# Input_channel.net
KiCad netlist of a schematic drawn in Altium Designer
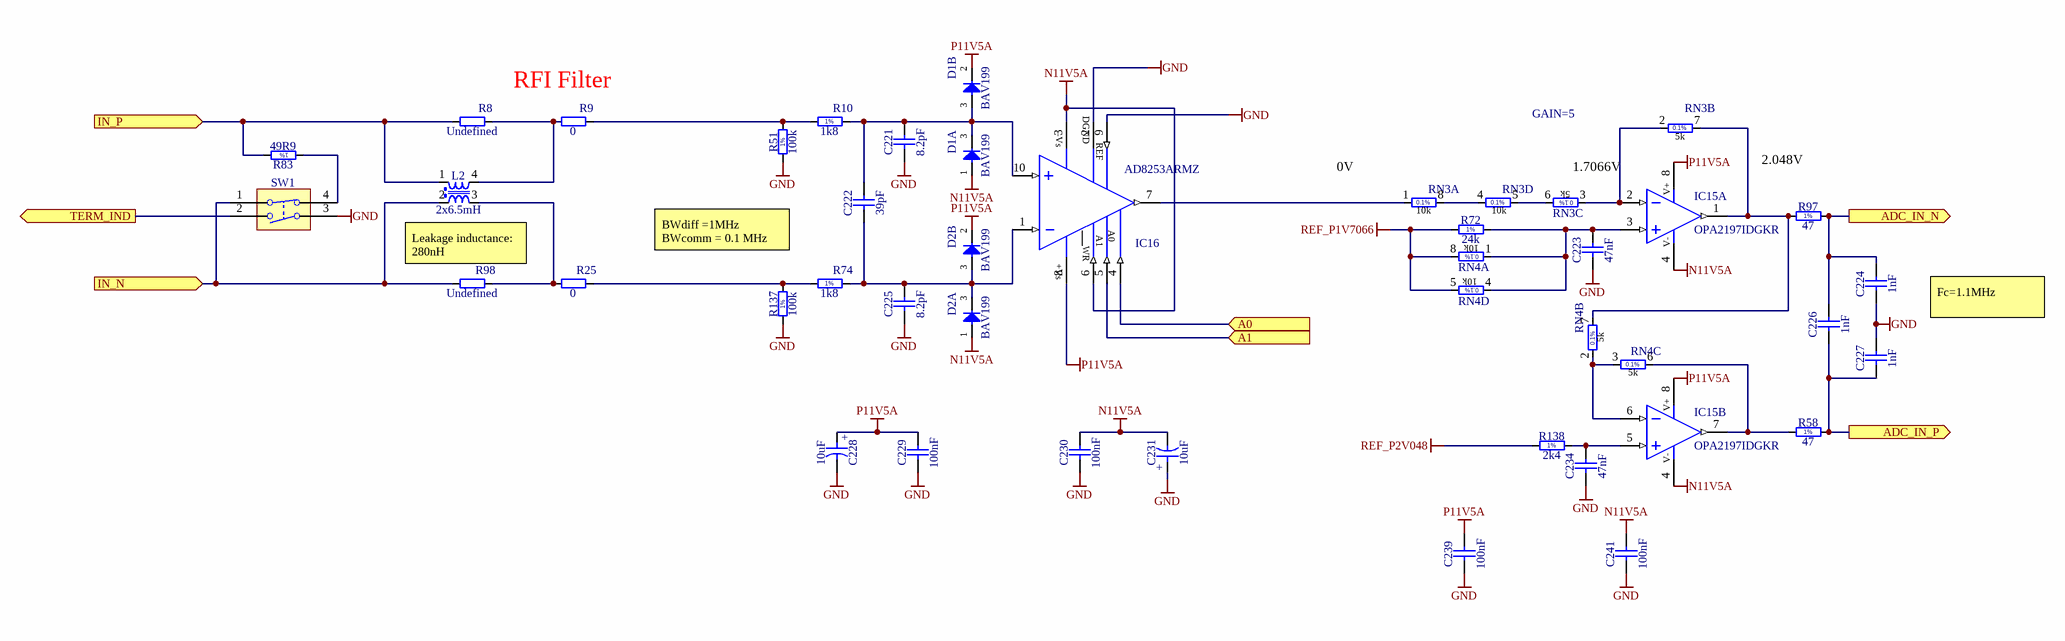
[diagram p0: Input_channel.SchDoc]

(export (version "E")
  (design (tool "Eeschema 10.0.6"))
  (components
    (comp (ref "C221")
      (value "8.2pF")
      (footprint "CAPC1608X87N")
      (description "Non-polarised capacitor")
      (fields
        (field (name "PART NUMBER") "CC0603_8.2PF_50V_0.5PF_NP0")
        (field (name "VOLTAGE") "50V")
        (field (name "AUTHOR") "CERN DEM JLC")
      )
      (libsource (lib "Capacitors") (part "Capacitor - non polarized"))
    )
    (comp (ref "C222")
      (value "39pF")
      (footprint "CAPC1608X87N")
      (description "Non-polarised capacitor")
      (fields
        (field (name "PART NUMBER") "CC0603_39PF_50V_5%_NP0")
        (field (name "VOLTAGE") "50V")
        (field (name "AUTHOR") "CERN DEM JLC")
      )
      (libsource (lib "Capacitors") (part "Capacitor - non polarized"))
    )
    (comp (ref "C223")
      (value "47nF")
      (footprint "CAPC2012X135N")
      (description "Non-polarised capacitor")
      (fields
        (field (name "PART NUMBER") "CC0805_47NF_25V_5%_C0G")
        (field (name "VOLTAGE") "25V")
        (field (name "AUTHOR") "CERN DEM JLC")
      )
      (libsource (lib "Capacitors") (part "Capacitor - non polarized"))
    )
    (comp (ref "C224")
      (value "1nF")
      (footprint "CAPC1608X90N")
      (description "Non-polarised capacitor")
      (fields
        (field (name "PART NUMBER") "CC0603_1NF_50V_1%_NP0")
        (field (name "VOLTAGE") "50V")
        (field (name "AUTHOR") "CERN DEM JLC")
      )
      (libsource (lib "Capacitors") (part "Capacitor - non polarized"))
    )
    (comp (ref "C225")
      (value "8.2pF")
      (footprint "CAPC1608X87N")
      (description "Non-polarised capacitor")
      (fields
        (field (name "PART NUMBER") "CC0603_8.2PF_50V_0.5PF_NP0")
        (field (name "VOLTAGE") "50V")
        (field (name "AUTHOR") "CERN DEM JLC")
      )
      (libsource (lib "Capacitors") (part "Capacitor - non polarized"))
    )
    (comp (ref "C226")
      (value "1nF")
      (footprint "CAPC1608X90N")
      (description "Non-polarised capacitor")
      (fields
        (field (name "PART NUMBER") "CC0603_1NF_50V_1%_NP0")
        (field (name "VOLTAGE") "50V")
        (field (name "AUTHOR") "CERN DEM JLC")
      )
      (libsource (lib "Capacitors") (part "Capacitor - non polarized"))
    )
    (comp (ref "C227")
      (value "1nF")
      (footprint "CAPC1608X90N")
      (description "Non-polarised capacitor")
      (fields
        (field (name "PART NUMBER") "CC0603_1NF_50V_1%_NP0")
        (field (name "VOLTAGE") "50V")
        (field (name "AUTHOR") "CERN DEM JLC")
      )
      (libsource (lib "Capacitors") (part "Capacitor - non polarized"))
    )
    (comp (ref "C228")
      (value "10uF")
      (footprint "CAPMP3216X180N")
      (description "Polarised capacitor")
      (fields
        (field (name "PART NUMBER") "CTE3216-18_10UF_16V_20%_AVX_TCJ")
        (field (name "VOLTAGE") "16V")
        (field (name "AUTHOR") "CERN DEM JLC")
      )
      (libsource (lib "Capacitors") (part "Capacitor - polarized"))
    )
    (comp (ref "C229")
      (value "100nF")
      (footprint "CAPC1005X55N")
      (description "Non-polarised capacitor")
      (fields
        (field (name "PART NUMBER") "CC0402_100NF_16V_10%_X7R")
        (field (name "VOLTAGE") "16V")
        (field (name "AUTHOR") "CERN DEM JLC")
      )
      (libsource (lib "Capacitors") (part "Capacitor - non polarized"))
    )
    (comp (ref "C230")
      (value "100nF")
      (footprint "CAPC1005X55N")
      (description "Non-polarised capacitor")
      (fields
        (field (name "PART NUMBER") "CC0402_100NF_16V_10%_X7R")
        (field (name "VOLTAGE") "16V")
        (field (name "AUTHOR") "CERN DEM JLC")
      )
      (libsource (lib "Capacitors") (part "Capacitor - non polarized"))
    )
    (comp (ref "C231")
      (value "10uF")
      (footprint "CAPMP3216X180N")
      (description "Polarised capacitor")
      (fields
        (field (name "PART NUMBER") "CTE3216-18_10UF_16V_20%_AVX_TCJ")
        (field (name "VOLTAGE") "16V")
        (field (name "AUTHOR") "CERN DEM JLC")
      )
      (libsource (lib "Capacitors") (part "Capacitor - polarized"))
    )
    (comp (ref "C234")
      (value "47nF")
      (footprint "CAPC2012X135N")
      (description "Non-polarised capacitor")
      (fields
        (field (name "PART NUMBER") "CC0805_47NF_25V_5%_C0G")
        (field (name "VOLTAGE") "25V")
        (field (name "AUTHOR") "CERN DEM JLC")
      )
      (libsource (lib "Capacitors") (part "Capacitor - non polarized"))
    )
    (comp (ref "C239")
      (value "100nF")
      (footprint "CAPC1005X55N")
      (description "Non-polarised capacitor")
      (fields
        (field (name "PART NUMBER") "CC0402_100NF_16V_10%_X7R")
        (field (name "VOLTAGE") "16V")
        (field (name "AUTHOR") "CERN DEM JLC")
      )
      (libsource (lib "Capacitors") (part "Capacitor - non polarized"))
    )
    (comp (ref "C241")
      (value "100nF")
      (footprint "CAPC1005X55N")
      (description "Non-polarised capacitor")
      (fields
        (field (name "PART NUMBER") "CC0402_100NF_16V_10%_X7R")
        (field (name "VOLTAGE") "16V")
        (field (name "AUTHOR") "CERN DEM JLC")
      )
      (libsource (lib "Capacitors") (part "Capacitor - non polarized"))
    )
    (comp (ref "D1")
      (value "BAV199")
      (footprint "SOT95P240X110-3N")
      (description "Serial Diode")
      (fields
        (field (name "VOLTAGE") "75V")
        (field (name "POWER") "250mW")
        (field (name "AUTHOR") "CERN DEM JMW")
      )
      (libsource (lib "ICs And Semiconductors") (part "Diode x2 A1C3_A3C2"))
    )
    (comp (ref "D2")
      (value "BAV199")
      (footprint "SOT95P240X110-3N")
      (description "Serial Diode")
      (fields
        (field (name "VOLTAGE") "75V")
        (field (name "POWER") "250mW")
        (field (name "AUTHOR") "CERN DEM JMW")
      )
      (libsource (lib "ICs And Semiconductors") (part "Diode x2 A1C3_A3C2"))
    )
    (comp (ref "IC15")
      (value "OPA2197IDGKR")
      (footprint "SOP65P490X110-8N")
      (description "36-V, Precision, Rail-to-Rail Input Output, Low Offset Voltage Op Amp 8-VSSOP")
      (fields (field (name "MANUFACTURER") "TEXAS INSTRUMENTS") (field (name "AUTHOR") "GK"))
      (libsource (lib "LIBRARY_SCH") (part "OA_OPA2197IDGKR"))
    )
    (comp (ref "IC16")
      (value "AD8253ARMZ")
      (footprint "SOP50P490X110-10N")
      (description "10MHz, 20V/us, G= 1, 10, 100, 1000 iCMOS Programmable Gain Instrumentation Amplifier")
      (fields (field (name "MANUFACTURER") "ANALOG DEVICES") (field (name "AUTHOR") "CERN DEM JLC"))
      (libsource (lib "ICs And Semiconductors") (part "AD8253"))
    )
    (comp (ref "L2")
      (value "2x6.5mH")
      (footprint "IND_WURTH_WE-SL2")
      (description "Inductor Common Mode")
      (fields
        (field (name "PART NUMBER") "IND_6.5MH_50%_WURTH_WE-SL2-744229")
        (field (name "POWER") "400mA")
        (field (name "AUTHOR") "CERN DEM JLC")
      )
      (libsource (lib "Inductors & Transformers") (part "Inductor Common Mode 1Dot-4 2Dot-3"))
    )
    (comp (ref "R8")
      (value "Undefined")
      (footprint "RESC1608X55N")
      (description "Resistor")
      (fields (field (name "PART NUMBER") "R0603_NO-VALUE") (field (name "AUTHOR") "CERN DEM JLC"))
      (libsource (lib "Resistors") (part "Resistor"))
    )
    (comp (ref "R9")
      (value "0")
      (footprint "RESC1608X55N")
      (description "Resistor")
      (fields
        (field (name "PART NUMBER") "R0603_0R_JUMPER")
        (field (name "MANUFACTURER") "GENERIC")
        (field (name "AUTHOR") "CERN DEM JLC")
      )
      (libsource (lib "Resistors") (part "Resistor"))
    )
    (comp (ref "R10")
      (value "1k8")
      (footprint "RESC1608X55N")
      (description "Resistor - 1%")
      (fields
        (field (name "PART NUMBER") "R0603_1K8_1%_0.1W_100PPM")
        (field (name "POWER") "0.1W")
        (field (name "AUTHOR") "CERN DEM JLC")
      )
      (libsource (lib "Resistors") (part "Resistor - 1%"))
    )
    (comp (ref "R25")
      (value "0")
      (footprint "RESC1608X55N")
      (description "Resistor")
      (fields
        (field (name "PART NUMBER") "R0603_0R_JUMPER")
        (field (name "MANUFACTURER") "GENERIC")
        (field (name "AUTHOR") "CERN DEM JLC")
      )
      (libsource (lib "Resistors") (part "Resistor"))
    )
    (comp (ref "R51")
      (value "100k")
      (footprint "RESC1608X55N")
      (description "Resistor - 1%")
      (fields
        (field (name "PART NUMBER") "R0603_100K_1%_0.1W_100PPM")
        (field (name "POWER") "0.1W")
        (field (name "AUTHOR") "CERN DEM JLC")
      )
      (libsource (lib "Resistors") (part "Resistor - 1%"))
    )
    (comp (ref "R58")
      (value "47")
      (footprint "RESC1005X40N")
      (description "Resistor - 1%")
      (fields
        (field (name "PART NUMBER") "R0402_47R_1%_0.0625W_100PPM")
        (field (name "POWER") "0.0625W")
        (field (name "AUTHOR") "CERN DEM JLC")
      )
      (libsource (lib "Resistors") (part "Resistor - 1%"))
    )
    (comp (ref "R72")
      (value "24k")
      (footprint "RESC1608X55N")
      (description "Resistor - 1%")
      (fields
        (field (name "PART NUMBER") "R0603_24K_1%_0.1W_100PPM")
        (field (name "POWER") "0.1W")
        (field (name "AUTHOR") "CERN DEM JLC")
      )
      (libsource (lib "Resistors") (part "Resistor - 1%"))
    )
    (comp (ref "R74")
      (value "1k8")
      (footprint "RESC1608X55N")
      (description "Resistor - 1%")
      (fields
        (field (name "PART NUMBER") "R0603_1K8_1%_0.1W_100PPM")
        (field (name "POWER") "0.1W")
        (field (name "AUTHOR") "CERN DEM JLC")
      )
      (libsource (lib "Resistors") (part "Resistor - 1%"))
    )
    (comp (ref "R83")
      (value "49R9")
      (footprint "RESC6331X70N")
      (description "Resistor - 1%")
      (fields
        (field (name "PART NUMBER") "R2512_49R9_1%_1W_100PPM_VISHAY_CRCW")
        (field (name "POWER") "1W")
        (field (name "AUTHOR") "CERN DEM JLC")
      )
      (libsource (lib "Resistors") (part "Resistor - 1%"))
    )
    (comp (ref "R97")
      (value "47")
      (footprint "RESC1005X40N")
      (description "Resistor - 1%")
      (fields
        (field (name "PART NUMBER") "R0402_47R_1%_0.0625W_100PPM")
        (field (name "POWER") "0.0625W")
        (field (name "AUTHOR") "CERN DEM JLC")
      )
      (libsource (lib "Resistors") (part "Resistor - 1%"))
    )
    (comp (ref "R98")
      (value "Undefined")
      (footprint "RESC1608X55N")
      (description "Resistor")
      (fields (field (name "PART NUMBER") "R0603_NO-VALUE") (field (name "AUTHOR") "CERN DEM JLC"))
      (libsource (lib "Resistors") (part "Resistor"))
    )
    (comp (ref "R137")
      (value "100k")
      (footprint "RESC1608X55N")
      (description "Resistor - 1%")
      (fields
        (field (name "PART NUMBER") "R0603_100K_1%_0.1W_100PPM")
        (field (name "POWER") "0.1W")
        (field (name "AUTHOR") "CERN DEM JLC")
      )
      (libsource (lib "Resistors") (part "Resistor - 1%"))
    )
    (comp (ref "R138")
      (value "2k4")
      (footprint "RESC1005X40N")
      (description "Resistor - 1%")
      (fields
        (field (name "PART NUMBER") "R0402_2K4_1%_0.0625W_100PPM")
        (field (name "POWER") "0.0625W")
        (field (name "AUTHOR") "CERN DEM JLC")
      )
      (libsource (lib "Resistors") (part "Resistor - 1%"))
    )
    (comp (ref "RN3")
      (value "10k 5K 5K 10K")
      (footprint "SOIC127P600X175-8N")
      (description "DIL8 Resistor Network 4 Resistors 10k-5k-5k-10k 0.1%")
      (fields
        (field (name "PART NUMBER") "RN_10K_5K_VISHAY_AORN2-1AT3")
        (field (name "POWER") "4x0.1W")
        (field (name "AUTHOR") "CERN DEM JLC")
      )
      (libsource (lib "Resistors") (part "RN DIL8_4xR_10k-5k-5k-10k_0.1%"))
    )
    (comp (ref "RN4")
      (value "10k 5K 5K 10K")
      (footprint "SOIC127P600X175-8N")
      (description "DIL8 Resistor Network 4 Resistors 10k-5k-5k-10k 0.1%")
      (fields
        (field (name "PART NUMBER") "RN_10K_5K_VISHAY_AORN2-1AT3")
        (field (name "POWER") "4x0.1W")
        (field (name "AUTHOR") "CERN DEM JLC")
      )
      (libsource (lib "Resistors") (part "RN DIL8_4xR_10k-5k-5k-10k_0.1%"))
    )
    (comp (ref "SW1")
      (value "Switch")
      (footprint "SW_CTS_204-121ST")
      (description "2x SPST DIP Switch 1NO + 1NF")
      (fields
        (field (name "PART NUMBER") "SW_CTS_204-121ST")
        (field (name "MANUFACTURER") "CTS")
        (field (name "AUTHOR") "CERN DEM JLC")
      )
      (libsource (lib "Eletro-mechanical") (part "SW_CTS_204-121ST"))
    )
  )
  (nets
    (net (code "1") (name "/A0") (class "Default")
      (node (ref "IC16") (pin "4") (pinfunction "A0_4") (pintype "input"))
    )
    (net (code "2") (name "/A1") (class "Default")
      (node (ref "IC16") (pin "5") (pinfunction "A1_5") (pintype "input"))
    )
    (net (code "3") (name "/ADC_IN_N") (class "Default")
      (node (ref "C224") (pin "2") (pinfunction "2_2") (pintype "passive"))
      (node (ref "C226") (pin "2") (pinfunction "2_2") (pintype "passive"))
      (node (ref "R97") (pin "2") (pinfunction "2_2") (pintype "passive"))
    )
    (net (code "4") (name "/ADC_IN_P") (class "Default")
      (node (ref "C226") (pin "1") (pinfunction "1_1") (pintype "passive"))
      (node (ref "C227") (pin "1") (pinfunction "1_1") (pintype "passive"))
      (node (ref "R58") (pin "2") (pinfunction "2_2") (pintype "passive"))
    )
    (net (code "5") (name "/IN_N") (class "Default")
      (node (ref "L2") (pin "2") (pinfunction "2_2") (pintype "passive"))
      (node (ref "R98") (pin "1") (pinfunction "1_1") (pintype "passive"))
      (node (ref "SW1") (pin "1") (pinfunction "1_1") (pintype "passive"))
    )
    (net (code "6") (name "/IN_P") (class "Default")
      (node (ref "L2") (pin "1") (pinfunction "1_1") (pintype "passive"))
      (node (ref "R8") (pin "1") (pinfunction "1_1") (pintype "passive"))
      (node (ref "R83") (pin "2") (pinfunction "2_2") (pintype "passive"))
    )
    (net (code "7") (name "/TERM_IND") (class "Default")
      (node (ref "SW1") (pin "2") (pinfunction "2_2") (pintype "passive"))
    )
    (net (code "8") (name "GND") (class "Default")
      (node (ref "C221") (pin "1") (pinfunction "1_1") (pintype "passive"))
      (node (ref "C223") (pin "1") (pinfunction "1_1") (pintype "passive"))
      (node (ref "C224") (pin "1") (pinfunction "1_1") (pintype "passive"))
      (node (ref "C225") (pin "1") (pinfunction "1_1") (pintype "passive"))
      (node (ref "C227") (pin "2") (pinfunction "2_2") (pintype "passive"))
      (node (ref "C228") (pin "2") (pinfunction "2_2") (pintype "passive"))
      (node (ref "C229") (pin "1") (pinfunction "1_1") (pintype "passive"))
      (node (ref "C230") (pin "1") (pinfunction "1_1") (pintype "passive"))
      (node (ref "C231") (pin "1") (pinfunction "1_1") (pintype "passive"))
      (node (ref "C234") (pin "1") (pinfunction "1_1") (pintype "passive"))
      (node (ref "C239") (pin "1") (pinfunction "1_1") (pintype "passive"))
      (node (ref "C241") (pin "1") (pinfunction "1_1") (pintype "passive"))
      (node (ref "IC16") (pin "2") (pinfunction "DGND_2") (pintype "power_in"))
      (node (ref "IC16") (pin "9") (pinfunction "REF_9") (pintype "input"))
      (node (ref "R137") (pin "1") (pinfunction "1_1") (pintype "passive"))
      (node (ref "R51") (pin "1") (pinfunction "1_1") (pintype "passive"))
      (node (ref "SW1") (pin "3") (pinfunction "3_3") (pintype "passive"))
    )
    (net (code "9") (name "N11V5A") (class "Default")
      (node (ref "C230") (pin "2") (pinfunction "2_2") (pintype "passive"))
      (node (ref "C231") (pin "2") (pinfunction "2_2") (pintype "passive"))
      (node (ref "C241") (pin "2") (pinfunction "2_2") (pintype "passive"))
      (node (ref "D1") (pin "1") (pinfunction "A_1") (pintype "passive"))
      (node (ref "D2") (pin "1") (pinfunction "A_1") (pintype "passive"))
      (node (ref "IC15") (pin "4") (pinfunction "V-_4") (pintype "power_in"))
      (node (ref "IC16") (pin "3") (pinfunction "-VS_3") (pintype "power_in"))
      (node (ref "IC16") (pin "6") (pinfunction "~{WR}_6") (pintype "input"))
    )
    (net (code "10") (name "Net-(D1A-COMAC)") (class "Default")
      (node (ref "C221") (pin "2") (pinfunction "2_2") (pintype "passive"))
      (node (ref "C222") (pin "2") (pinfunction "2_2") (pintype "passive"))
      (node (ref "D1") (pin "3") (pinfunction "COMAC_3") (pintype "passive"))
      (node (ref "IC16") (pin "10") (pinfunction "+IN_10") (pintype "input"))
      (node (ref "R10") (pin "2") (pinfunction "2_2") (pintype "passive"))
    )
    (net (code "11") (name "Net-(D2A-COMAC)") (class "Default")
      (node (ref "C222") (pin "1") (pinfunction "1_1") (pintype "passive"))
      (node (ref "C225") (pin "2") (pinfunction "2_2") (pintype "passive"))
      (node (ref "D2") (pin "3") (pinfunction "COMAC_3") (pintype "passive"))
      (node (ref "IC16") (pin "1") (pinfunction "-IN_1") (pintype "input"))
      (node (ref "R74") (pin "2") (pinfunction "2_2") (pintype "passive"))
    )
    (net (code "12") (name "Net-(IC15A-IN+)") (class "Default")
      (node (ref "C223") (pin "2") (pinfunction "2_2") (pintype "passive"))
      (node (ref "IC15") (pin "3") (pinfunction "IN+_3") (pintype "input"))
      (node (ref "R72") (pin "2") (pinfunction "2_2") (pintype "passive"))
      (node (ref "RN4") (pin "1") (pinfunction "1_1") (pintype "passive"))
      (node (ref "RN4") (pin "4") (pinfunction "4_4") (pintype "passive"))
    )
    (net (code "13") (name "Net-(IC15A-IN-)") (class "Default")
      (node (ref "IC15") (pin "2") (pinfunction "IN-_2") (pintype "input"))
      (node (ref "RN3") (pin "2") (pinfunction "2_2") (pintype "passive"))
      (node (ref "RN3") (pin "3") (pinfunction "3_3") (pintype "passive"))
    )
    (net (code "14") (name "Net-(IC15A-OUT)") (class "Default")
      (node (ref "IC15") (pin "1") (pinfunction "OUT_1") (pintype "output"))
      (node (ref "R97") (pin "1") (pinfunction "1_1") (pintype "passive"))
      (node (ref "RN3") (pin "7") (pinfunction "7_7") (pintype "passive"))
      (node (ref "RN4") (pin "7") (pinfunction "7_7") (pintype "passive"))
    )
    (net (code "15") (name "Net-(IC15B-IN+)") (class "Default")
      (node (ref "C234") (pin "2") (pinfunction "2_2") (pintype "passive"))
      (node (ref "IC15") (pin "5") (pinfunction "IN+_5") (pintype "input"))
      (node (ref "R138") (pin "2") (pinfunction "2_2") (pintype "passive"))
    )
    (net (code "16") (name "Net-(IC15B-IN-)") (class "Default")
      (node (ref "IC15") (pin "6") (pinfunction "IN-_6") (pintype "input"))
      (node (ref "RN4") (pin "2") (pinfunction "2_2") (pintype "passive"))
      (node (ref "RN4") (pin "3") (pinfunction "3_3") (pintype "passive"))
    )
    (net (code "17") (name "Net-(IC15B-OUT)") (class "Default")
      (node (ref "IC15") (pin "7") (pinfunction "OUT_7") (pintype "output"))
      (node (ref "R58") (pin "1") (pinfunction "1_1") (pintype "passive"))
      (node (ref "RN4") (pin "6") (pinfunction "6_6") (pintype "passive"))
    )
    (net (code "18") (name "Net-(IC16-OUT)") (class "Default")
      (node (ref "IC16") (pin "7") (pinfunction "OUT_7") (pintype "output"))
      (node (ref "RN3") (pin "1") (pinfunction "1_1") (pintype "passive"))
    )
    (net (code "19") (name "Net-(L2-Pad3)") (class "Default")
      (node (ref "L2") (pin "3") (pinfunction "3_3") (pintype "passive"))
      (node (ref "R25") (pin "1") (pinfunction "1_1") (pintype "passive"))
      (node (ref "R98") (pin "2") (pinfunction "2_2") (pintype "passive"))
    )
    (net (code "20") (name "Net-(L2-Pad4)") (class "Default")
      (node (ref "L2") (pin "4") (pinfunction "4_4") (pintype "passive"))
      (node (ref "R8") (pin "2") (pinfunction "2_2") (pintype "passive"))
      (node (ref "R9") (pin "1") (pinfunction "1_1") (pintype "passive"))
    )
    (net (code "21") (name "Net-(R10-Pad1)") (class "Default")
      (node (ref "R10") (pin "1") (pinfunction "1_1") (pintype "passive"))
      (node (ref "R51") (pin "2") (pinfunction "2_2") (pintype "passive"))
      (node (ref "R9") (pin "2") (pinfunction "2_2") (pintype "passive"))
    )
    (net (code "22") (name "Net-(R83-Pad1)") (class "Default")
      (node (ref "R83") (pin "1") (pinfunction "1_1") (pintype "passive"))
      (node (ref "SW1") (pin "4") (pinfunction "4_4") (pintype "passive"))
    )
    (net (code "23") (name "Net-(R137-Pad2)") (class "Default")
      (node (ref "R137") (pin "2") (pinfunction "2_2") (pintype "passive"))
      (node (ref "R25") (pin "2") (pinfunction "2_2") (pintype "passive"))
      (node (ref "R74") (pin "1") (pinfunction "1_1") (pintype "passive"))
    )
    (net (code "24") (name "Net-(RN3-Pad4)") (class "Default")
      (node (ref "RN3") (pin "4") (pinfunction "4_4") (pintype "passive"))
      (node (ref "RN3") (pin "8") (pinfunction "8_8") (pintype "passive"))
    )
    (net (code "25") (name "Net-(RN3-Pad5)") (class "Default")
      (node (ref "RN3") (pin "5") (pinfunction "5_5") (pintype "passive"))
      (node (ref "RN3") (pin "6") (pinfunction "6_6") (pintype "passive"))
    )
    (net (code "26") (name "P11V5A") (class "Default")
      (node (ref "C228") (pin "1") (pinfunction "1_1") (pintype "passive"))
      (node (ref "C229") (pin "2") (pinfunction "2_2") (pintype "passive"))
      (node (ref "C239") (pin "2") (pinfunction "2_2") (pintype "passive"))
      (node (ref "D1") (pin "2") (pinfunction "C_2") (pintype "passive"))
      (node (ref "D2") (pin "2") (pinfunction "C_2") (pintype "passive"))
      (node (ref "IC15") (pin "8") (pinfunction "V+_8") (pintype "power_in"))
      (node (ref "IC16") (pin "8") (pinfunction "+VS_8") (pintype "power_in"))
    )
    (net (code "27") (name "REF_P1V7066") (class "Default")
      (node (ref "R72") (pin "1") (pinfunction "1_1") (pintype "passive"))
      (node (ref "RN4") (pin "5") (pinfunction "5_5") (pintype "passive"))
      (node (ref "RN4") (pin "8") (pinfunction "8_8") (pintype "passive"))
    )
    (net (code "28") (name "REF_P2V048") (class "Default")
      (node (ref "R138") (pin "1") (pinfunction "1_1") (pintype "passive"))
    )
  )
)
